# saksi.net
KiCad netlist of a schematic drawn in EAGLE
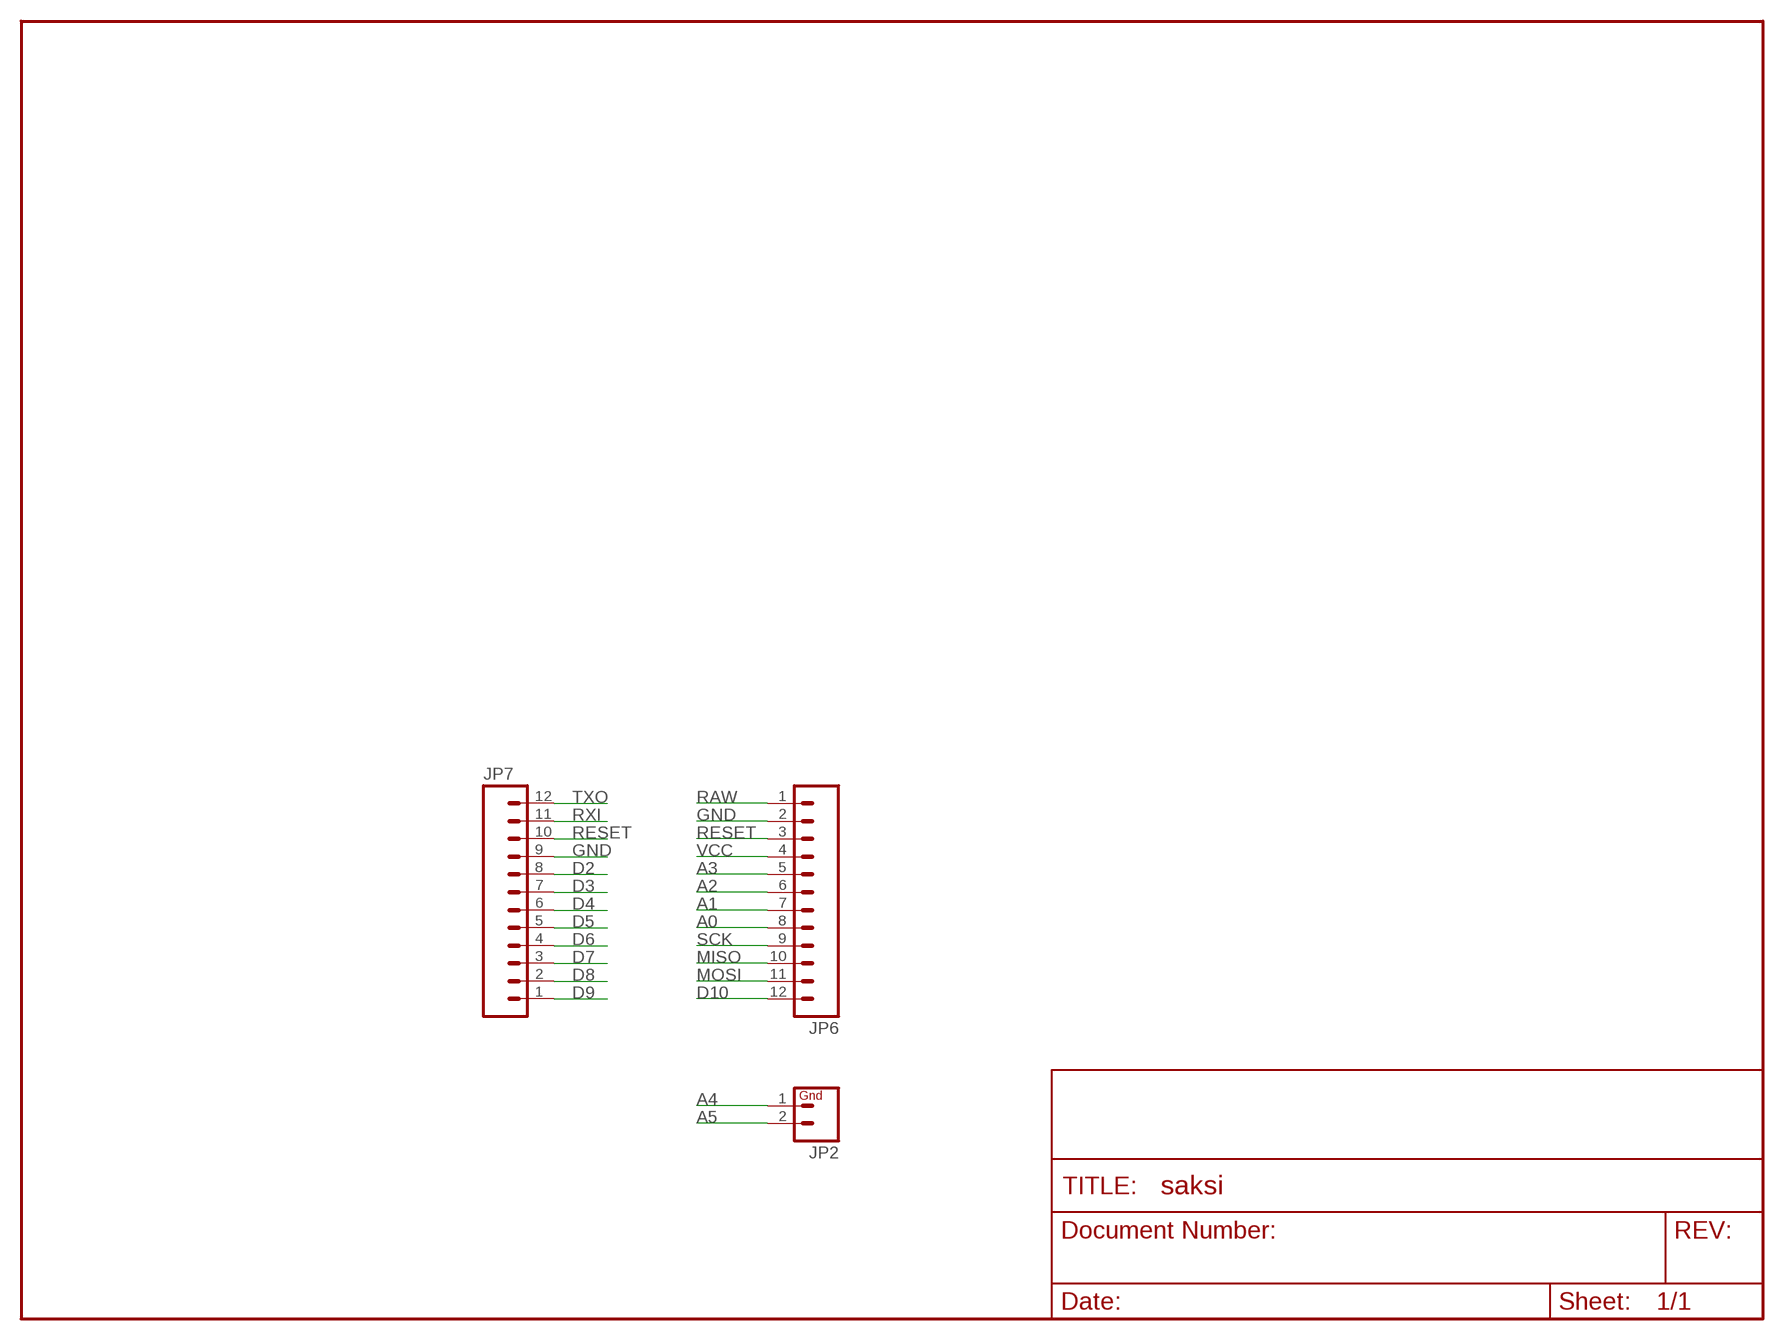
[diagram p0: schematic, sheet 1]

(export (version "E")
  (design (tool "Eeschema 10.0.6"))
  (components
    (comp (ref "JP2")
      (value "M02PTH")
      (footprint "eagle-import:1X02")
      (libsource (lib "eagle-import") (part "M02PTH"))
    )
    (comp (ref "JP6")
      (value "M12PTH")
      (footprint "eagle-import:1X12")
      (libsource (lib "eagle-import") (part "M12PTH"))
    )
    (comp (ref "JP7")
      (value "M12PTH")
      (footprint "eagle-import:1X12")
      (libsource (lib "eagle-import") (part "M12PTH"))
    )
  )
  (nets
    (net (code "1") (name "/A0") (class "Default")
      (node (ref "JP6") (pin "8") (pinfunction "8_8") (pintype "passive"))
    )
    (net (code "2") (name "/A1") (class "Default")
      (node (ref "JP6") (pin "7") (pinfunction "7_7") (pintype "passive"))
    )
    (net (code "3") (name "/A2") (class "Default")
      (node (ref "JP6") (pin "6") (pinfunction "6_6") (pintype "passive"))
    )
    (net (code "4") (name "/A3") (class "Default")
      (node (ref "JP6") (pin "5") (pinfunction "5_5") (pintype "passive"))
    )
    (net (code "5") (name "/A4") (class "Default")
      (node (ref "JP2") (pin "1") (pinfunction "1_1") (pintype "passive"))
    )
    (net (code "6") (name "/A5") (class "Default")
      (node (ref "JP2") (pin "2") (pinfunction "2_2") (pintype "passive"))
    )
    (net (code "7") (name "/D2") (class "Default")
      (node (ref "JP7") (pin "8") (pinfunction "8_8") (pintype "passive"))
    )
    (net (code "8") (name "/D3") (class "Default")
      (node (ref "JP7") (pin "7") (pinfunction "7_7") (pintype "passive"))
    )
    (net (code "9") (name "/D4") (class "Default")
      (node (ref "JP7") (pin "6") (pinfunction "6_6") (pintype "passive"))
    )
    (net (code "10") (name "/D5") (class "Default")
      (node (ref "JP7") (pin "5") (pinfunction "5_5") (pintype "passive"))
    )
    (net (code "11") (name "/D6") (class "Default")
      (node (ref "JP7") (pin "4") (pinfunction "4_4") (pintype "passive"))
    )
    (net (code "12") (name "/D7") (class "Default")
      (node (ref "JP7") (pin "3") (pinfunction "3_3") (pintype "passive"))
    )
    (net (code "13") (name "/D8") (class "Default")
      (node (ref "JP7") (pin "2") (pinfunction "2_2") (pintype "passive"))
    )
    (net (code "14") (name "/D9") (class "Default")
      (node (ref "JP7") (pin "1") (pinfunction "1_1") (pintype "passive"))
    )
    (net (code "15") (name "/D10") (class "Default")
      (node (ref "JP6") (pin "12") (pinfunction "12_12") (pintype "passive"))
    )
    (net (code "16") (name "/GND") (class "Default")
      (node (ref "JP6") (pin "2") (pinfunction "2_2") (pintype "passive"))
      (node (ref "JP7") (pin "9") (pinfunction "9_9") (pintype "passive"))
    )
    (net (code "17") (name "/MISO") (class "Default")
      (node (ref "JP6") (pin "10") (pinfunction "10_10") (pintype "passive"))
    )
    (net (code "18") (name "/MOSI") (class "Default")
      (node (ref "JP6") (pin "11") (pinfunction "11_11") (pintype "passive"))
    )
    (net (code "19") (name "/RAW") (class "Default")
      (node (ref "JP6") (pin "1") (pinfunction "1_1") (pintype "passive"))
    )
    (net (code "20") (name "/RESET") (class "Default")
      (node (ref "JP6") (pin "3") (pinfunction "3_3") (pintype "passive"))
      (node (ref "JP7") (pin "10") (pinfunction "10_10") (pintype "passive"))
    )
    (net (code "21") (name "/RXI") (class "Default")
      (node (ref "JP7") (pin "11") (pinfunction "11_11") (pintype "passive"))
    )
    (net (code "22") (name "/SCK") (class "Default")
      (node (ref "JP6") (pin "9") (pinfunction "9_9") (pintype "passive"))
    )
    (net (code "23") (name "/TXO") (class "Default")
      (node (ref "JP7") (pin "12") (pinfunction "12_12") (pintype "passive"))
    )
    (net (code "24") (name "/VCC") (class "Default")
      (node (ref "JP6") (pin "4") (pinfunction "4_4") (pintype "passive"))
    )
  )
)
